# main_board.net
KiCad netlist of a schematic drawn in EAGLE
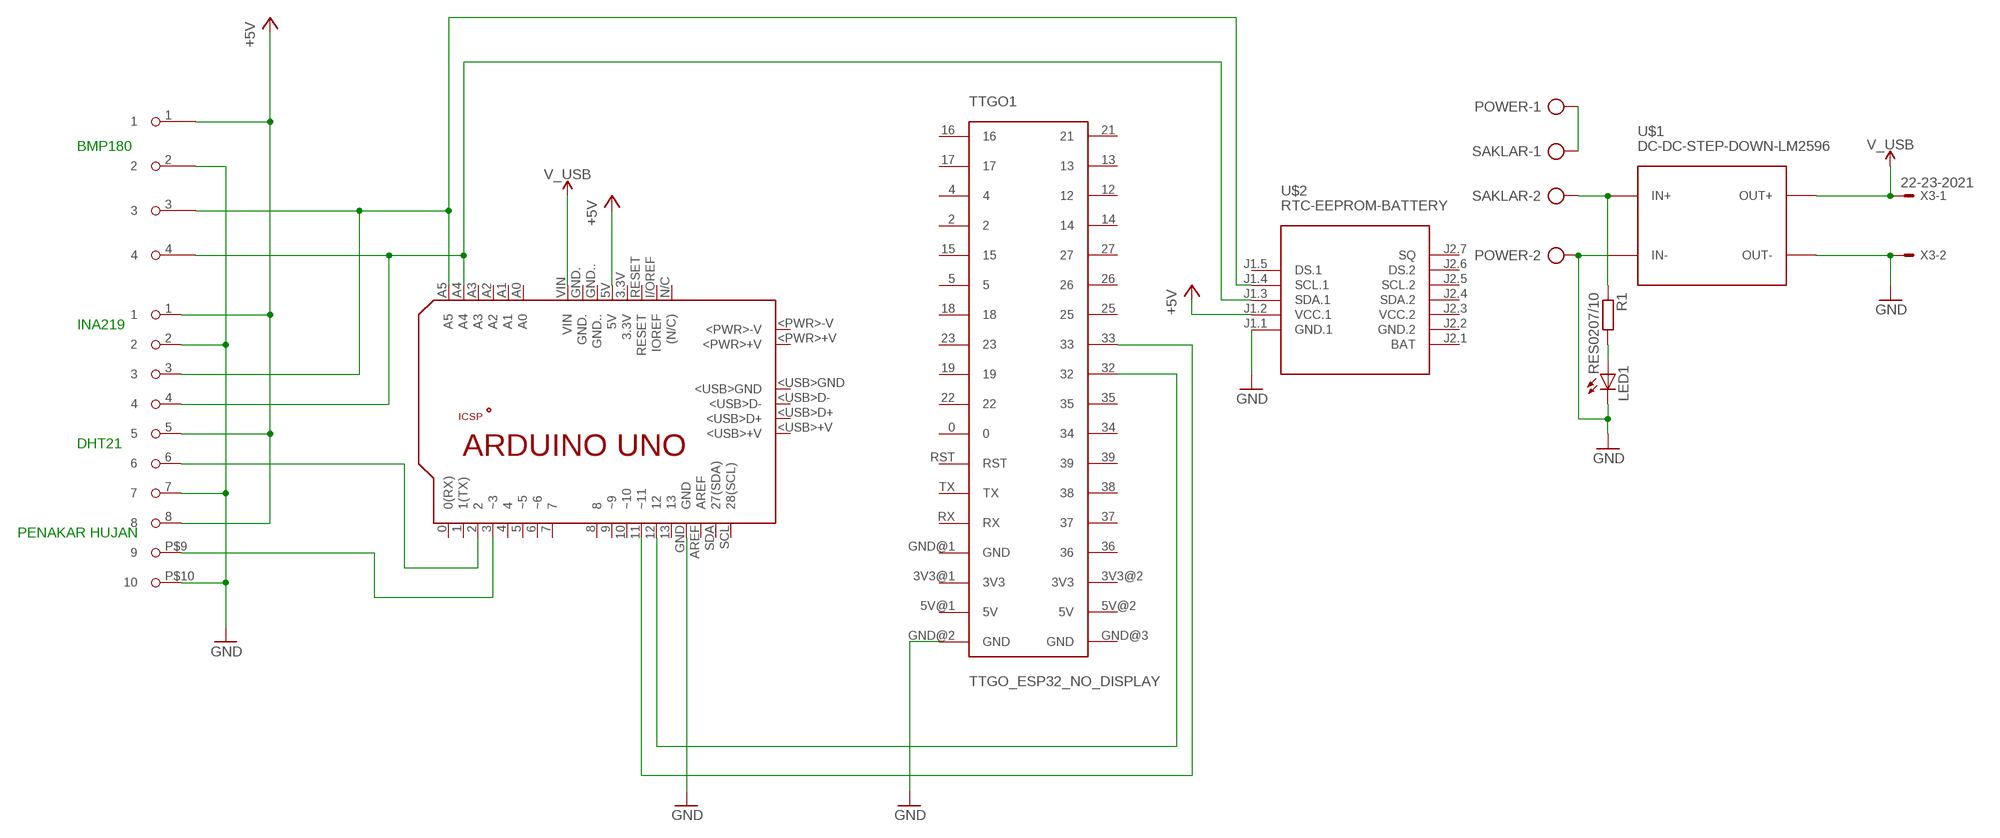
[diagram p0: schematic, sheet 1]

(export (version "E")
  (design (tool "Eeschema 10.0.6"))
  (components
    (comp (ref "LED1")
      (value "LED5MM")
      (footprint "eagle-import:LED5MM")
      (libsource (lib "eagle-import") (part "LED5MM"))
    )
    (comp (ref "PCB1")
      (value "ARDUINO_UNO")
      (footprint "eagle-import:ARDUINO_UNO")
      (libsource (lib "eagle-import") (part "ARDUINO_UNO"))
    )
    (comp (ref "POWER")
      (value "AK500/2-H")
      (footprint "eagle-import:AK500_2-H")
      (libsource (lib "eagle-import") (part "AK500/2-H"))
    )
    (comp (ref "R1")
      (value "RES0207/10")
      (footprint "eagle-import:0207_10")
      (libsource (lib "eagle-import") (part "RES0207/10"))
    )
    (comp (ref "SAKLAR")
      (value "AK500/2-H")
      (footprint "eagle-import:AK500_2-H")
      (libsource (lib "eagle-import") (part "AK500/2-H"))
    )
    (comp (ref "TTGO1")
      (value "TTGO_ESP32_NO_DISPLAY")
      (footprint "eagle-import:TTGO_ESP32_NO_DISPLAY")
      (libsource (lib "eagle-import") (part "TTGO_ESP32_NO_DISPLAY"))
    )
    (comp (ref "U$1")
      (value "DC-DC-STEP-DOWN-LM2596")
      (footprint "eagle-import:DC-DC-STEP-DOWN-LM2596")
      (libsource (lib "eagle-import") (part "DC-DC-STEP-DOWN-LM2596"))
    )
    (comp (ref "U$2")
      (value "RTC-EEPROM-BATTERY")
      (footprint "eagle-import:RTC-EEPROM-BATTERY")
      (libsource (lib "eagle-import") (part "RTC-EEPROM-BATTERY"))
    )
    (comp (ref "U$3")
      (value "CON-10TA")
      (footprint "eagle-import:CON-10TA")
      (libsource (lib "eagle-import") (part "CON-10TA"))
    )
    (comp (ref "U$4")
      (value "CON-4NEW2")
      (footprint "eagle-import:CON-4NEW")
      (libsource (lib "eagle-import") (part "CON-4NEW2"))
    )
    (comp (ref "X3")
      (value "22-23-2021")
      (footprint "eagle-import:22-23-2021")
      (fields (field (name "MF") "MOLEX"))
      (libsource (lib "eagle-import") (part "22-23-2021"))
    )
  )
  (nets
    (net (code "1") (name "+5V") (class "Default")
      (node (ref "PCB1") (pin "5V") (pinfunction "5V_5V") (pintype "bidirectional"))
      (node (ref "U$2") (pin "J1.2") (pinfunction "VCC.1_J1.2") (pintype "power_in"))
      (node (ref "U$3") (pin "1") (pinfunction "1_1") (pintype "bidirectional"))
      (node (ref "U$3") (pin "5") (pinfunction "5_5") (pintype "bidirectional"))
      (node (ref "U$3") (pin "8") (pinfunction "8_8") (pintype "bidirectional"))
      (node (ref "U$4") (pin "1") (pinfunction "1_1") (pintype "bidirectional"))
    )
    (net (code "2") (name "/GND.2") (class "Default")
      (node (ref "U$2") (pin "J2.2") (pinfunction "GND.2_J2.2") (pintype "power_in"))
    )
    (net (code "3") (name "/VCC.2") (class "Default")
      (node (ref "U$2") (pin "J2.3") (pinfunction "VCC.2_J2.3") (pintype "power_in"))
    )
    (net (code "4") (name "GND") (class "Default")
      (node (ref "LED1") (pin "K") (pinfunction "C_K") (pintype "passive"))
      (node (ref "PCB1") (pin "GND") (pinfunction "GND_GND") (pintype "bidirectional"))
      (node (ref "POWER") (pin "2") (pinfunction "KL_2") (pintype "passive"))
      (node (ref "TTGO1") (pin "GND@2") (pinfunction "GND_GND@2") (pintype "bidirectional"))
      (node (ref "U$1") (pin "IN-") (pinfunction "IN-_IN-") (pintype "bidirectional"))
      (node (ref "U$1") (pin "OUT-") (pinfunction "OUT-_OUT-") (pintype "bidirectional"))
      (node (ref "U$2") (pin "J1.1") (pinfunction "GND.1_J1.1") (pintype "power_in"))
      (node (ref "U$3") (pin "2") (pinfunction "2_2") (pintype "bidirectional"))
      (node (ref "U$3") (pin "7") (pinfunction "7_7") (pintype "bidirectional"))
      (node (ref "U$3") (pin "P$10") (pinfunction "10_P$10") (pintype "bidirectional"))
      (node (ref "U$4") (pin "2") (pinfunction "2_2") (pintype "bidirectional"))
      (node (ref "X3") (pin "2") (pinfunction "S_2") (pintype "passive"))
    )
    (net (code "5") (name "Net-(LED1-PadA)") (class "Default")
      (node (ref "LED1") (pin "A") (pinfunction "A_A") (pintype "passive"))
      (node (ref "R1") (pin "2") (pinfunction "2_2") (pintype "passive"))
    )
    (net (code "6") (name "Net-(PCB1-Pad2)") (class "Default")
      (node (ref "PCB1") (pin "2") (pinfunction "2_2") (pintype "bidirectional"))
      (node (ref "U$3") (pin "6") (pinfunction "6_6") (pintype "bidirectional"))
    )
    (net (code "7") (name "Net-(PCB1-Pad12)") (class "Default")
      (node (ref "PCB1") (pin "12") (pinfunction "12_12") (pintype "bidirectional"))
      (node (ref "TTGO1") (pin "32") (pinfunction "32_32") (pintype "bidirectional"))
    )
    (net (code "8") (name "Net-(PCB1-~{3})") (class "Default")
      (node (ref "PCB1") (pin "3") (pinfunction "~{3}_3") (pintype "bidirectional"))
      (node (ref "U$3") (pin "P$9") (pinfunction "9_P$9") (pintype "bidirectional"))
    )
    (net (code "9") (name "Net-(PCB1-~{11})") (class "Default")
      (node (ref "PCB1") (pin "11") (pinfunction "~{11}_11") (pintype "bidirectional"))
      (node (ref "TTGO1") (pin "33") (pinfunction "33_33") (pintype "bidirectional"))
    )
    (net (code "10") (name "Net-(POWERA-KL)") (class "Default")
      (node (ref "POWER") (pin "1") (pinfunction "KL_1") (pintype "passive"))
      (node (ref "SAKLAR") (pin "1") (pinfunction "KL_1") (pintype "passive"))
    )
    (net (code "11") (name "Net-(SAKLARB-KL)") (class "Default")
      (node (ref "R1") (pin "1") (pinfunction "1_1") (pintype "passive"))
      (node (ref "SAKLAR") (pin "2") (pinfunction "KL_2") (pintype "passive"))
      (node (ref "U$1") (pin "IN+") (pinfunction "IN+_IN+") (pintype "bidirectional"))
    )
    (net (code "12") (name "Net-(U$2-SCL.1)") (class "Default")
      (node (ref "PCB1") (pin "A5") (pinfunction "A5_A5") (pintype "bidirectional"))
      (node (ref "U$2") (pin "J1.4") (pinfunction "SCL.1_J1.4") (pintype "bidirectional"))
      (node (ref "U$3") (pin "3") (pinfunction "3_3") (pintype "bidirectional"))
      (node (ref "U$4") (pin "3") (pinfunction "3_3") (pintype "bidirectional"))
    )
    (net (code "13") (name "Net-(U$2-SDA.1)") (class "Default")
      (node (ref "PCB1") (pin "A4") (pinfunction "A4_A4") (pintype "bidirectional"))
      (node (ref "U$2") (pin "J1.3") (pinfunction "SDA.1_J1.3") (pintype "bidirectional"))
      (node (ref "U$3") (pin "4") (pinfunction "4_4") (pintype "bidirectional"))
      (node (ref "U$4") (pin "4") (pinfunction "4_4") (pintype "bidirectional"))
    )
    (net (code "14") (name "V_USB") (class "Default")
      (node (ref "PCB1") (pin "VIN") (pinfunction "VIN_VIN") (pintype "bidirectional"))
      (node (ref "U$1") (pin "OUT+") (pinfunction "OUT+_OUT+") (pintype "bidirectional"))
      (node (ref "X3") (pin "1") (pinfunction "S_1") (pintype "passive"))
    )
    (net (code "15") (name "unconnected-(PCB1-(N{slash}C)-PadN{slash}C)") (class "Default")
      (node (ref "PCB1") (pin "N/C") (pinfunction "(N/C)_N/C") (pintype "bidirectional"))
    )
    (net (code "16") (name "unconnected-(PCB1-0(RX)-Pad0)") (class "Default")
      (node (ref "PCB1") (pin "0") (pinfunction "0(RX)_0") (pintype "bidirectional"))
    )
    (net (code "17") (name "unconnected-(PCB1-1(TX)-Pad1)") (class "Default")
      (node (ref "PCB1") (pin "1") (pinfunction "1(TX)_1") (pintype "bidirectional"))
    )
    (net (code "18") (name "unconnected-(PCB1-27(SDA)-PadSDA)") (class "Default")
      (node (ref "PCB1") (pin "SDA") (pinfunction "27(SDA)_SDA") (pintype "bidirectional"))
    )
    (net (code "19") (name "unconnected-(PCB1-28(SCL)-PadSCL)") (class "Default")
      (node (ref "PCB1") (pin "SCL") (pinfunction "28(SCL)_SCL") (pintype "bidirectional"))
    )
    (net (code "20") (name "unconnected-(PCB1-IOREF-PadI{slash}OREF)") (class "Default")
      (node (ref "PCB1") (pin "I/OREF") (pinfunction "IOREF_I/OREF") (pintype "bidirectional"))
    )
    (net (code "21") (name "unconnected-(PCB1-Pad+5V)") (class "Default")
      (node (ref "PCB1") (pin "+5V") (pinfunction "+5V_+5V") (pintype "bidirectional"))
    )
    (net (code "22") (name "unconnected-(PCB1-Pad3.3V)") (class "Default")
      (node (ref "PCB1") (pin "3.3V") (pinfunction "3.3V_3.3V") (pintype "bidirectional"))
    )
    (net (code "23") (name "unconnected-(PCB1-Pad4)") (class "Default")
      (node (ref "PCB1") (pin "4") (pinfunction "4_4") (pintype "bidirectional"))
    )
    (net (code "24") (name "unconnected-(PCB1-Pad7)") (class "Default")
      (node (ref "PCB1") (pin "7") (pinfunction "7_7") (pintype "bidirectional"))
    )
    (net (code "25") (name "unconnected-(PCB1-Pad8)") (class "Default")
      (node (ref "PCB1") (pin "8") (pinfunction "8_8") (pintype "bidirectional"))
    )
    (net (code "26") (name "unconnected-(PCB1-Pad13)") (class "Default")
      (node (ref "PCB1") (pin "13") (pinfunction "13_13") (pintype "bidirectional"))
    )
    (net (code "27") (name "unconnected-(PCB1-Pad<PWR>+V)") (class "Default")
      (node (ref "PCB1") (pin "<PWR>+V") (pinfunction "<PWR>+V_<PWR>+V") (pintype "bidirectional"))
    )
    (net (code "28") (name "unconnected-(PCB1-Pad<PWR>-V)") (class "Default")
      (node (ref "PCB1") (pin "<PWR>-V") (pinfunction "<PWR>-V_<PWR>-V") (pintype "bidirectional"))
    )
    (net (code "29") (name "unconnected-(PCB1-Pad<USB>+V)") (class "Default")
      (node (ref "PCB1") (pin "<USB>+V") (pinfunction "<USB>+V_<USB>+V") (pintype "bidirectional"))
    )
    (net (code "30") (name "unconnected-(PCB1-Pad<USB>D+)") (class "Default")
      (node (ref "PCB1") (pin "<USB>D+") (pinfunction "<USB>D+_<USB>D+") (pintype "bidirectional"))
    )
    (net (code "31") (name "unconnected-(PCB1-Pad<USB>D-)") (class "Default")
      (node (ref "PCB1") (pin "<USB>D-") (pinfunction "<USB>D-_<USB>D-") (pintype "bidirectional"))
    )
    (net (code "32") (name "unconnected-(PCB1-Pad<USB>GND)") (class "Default")
      (node (ref "PCB1") (pin "<USB>GND") (pinfunction "<USB>GND_<USB>GND") (pintype "bidirectional"))
    )
    (net (code "33") (name "unconnected-(PCB1-PadA0)") (class "Default")
      (node (ref "PCB1") (pin "A0") (pinfunction "A0_A0") (pintype "bidirectional"))
    )
    (net (code "34") (name "unconnected-(PCB1-PadA1)") (class "Default")
      (node (ref "PCB1") (pin "A1") (pinfunction "A1_A1") (pintype "bidirectional"))
    )
    (net (code "35") (name "unconnected-(PCB1-PadA2)") (class "Default")
      (node (ref "PCB1") (pin "A2") (pinfunction "A2_A2") (pintype "bidirectional"))
    )
    (net (code "36") (name "unconnected-(PCB1-PadA3)") (class "Default")
      (node (ref "PCB1") (pin "A3") (pinfunction "A3_A3") (pintype "bidirectional"))
    )
    (net (code "37") (name "unconnected-(PCB1-PadAREF)") (class "Default")
      (node (ref "PCB1") (pin "AREF") (pinfunction "AREF_AREF") (pintype "bidirectional"))
    )
    (net (code "38") (name "unconnected-(PCB1-PadGND.)") (class "Default")
      (node (ref "PCB1") (pin "GND.") (pinfunction "GND._GND.") (pintype "bidirectional"))
    )
    (net (code "39") (name "unconnected-(PCB1-PadGND..)") (class "Default")
      (node (ref "PCB1") (pin "GND..") (pinfunction "GND.._GND..") (pintype "bidirectional"))
    )
    (net (code "40") (name "unconnected-(PCB1-PadGND_)") (class "Default")
      (node (ref "PCB1") (pin "GND_") (pinfunction "GND__GND_") (pintype "bidirectional"))
    )
    (net (code "41") (name "unconnected-(PCB1-PadMISO)") (class "Default")
      (node (ref "PCB1") (pin "MISO") (pinfunction "MISO_MISO") (pintype "bidirectional"))
    )
    (net (code "42") (name "unconnected-(PCB1-PadMOSI)") (class "Default")
      (node (ref "PCB1") (pin "MOSI") (pinfunction "MOSI_MOSI") (pintype "bidirectional"))
    )
    (net (code "43") (name "unconnected-(PCB1-PadRESET)") (class "Default")
      (node (ref "PCB1") (pin "RESET") (pinfunction "RESET_RESET") (pintype "bidirectional"))
    )
    (net (code "44") (name "unconnected-(PCB1-PadRESET.)") (class "Default")
      (node (ref "PCB1") (pin "RESET.") (pinfunction "RESET._RESET.") (pintype "bidirectional"))
    )
    (net (code "45") (name "unconnected-(PCB1-PadSCK)") (class "Default")
      (node (ref "PCB1") (pin "SCK") (pinfunction "SCK_SCK") (pintype "bidirectional"))
    )
    (net (code "46") (name "unconnected-(PCB1-~{5}-Pad5)") (class "Default")
      (node (ref "PCB1") (pin "5") (pinfunction "~{5}_5") (pintype "bidirectional"))
    )
    (net (code "47") (name "unconnected-(PCB1-~{6}-Pad6)") (class "Default")
      (node (ref "PCB1") (pin "6") (pinfunction "~{6}_6") (pintype "bidirectional"))
    )
    (net (code "48") (name "unconnected-(PCB1-~{9}-Pad9)") (class "Default")
      (node (ref "PCB1") (pin "9") (pinfunction "~{9}_9") (pintype "bidirectional"))
    )
    (net (code "49") (name "unconnected-(PCB1-~{10}-Pad10)") (class "Default")
      (node (ref "PCB1") (pin "10") (pinfunction "~{10}_10") (pintype "bidirectional"))
    )
    (net (code "50") (name "unconnected-(TTGO1-3V3-Pad3V3@1)") (class "Default")
      (node (ref "TTGO1") (pin "3V3@1") (pinfunction "3V3_3V3@1") (pintype "bidirectional"))
    )
    (net (code "51") (name "unconnected-(TTGO1-3V3-Pad3V3@2)") (class "Default")
      (node (ref "TTGO1") (pin "3V3@2") (pinfunction "3V3_3V3@2") (pintype "bidirectional"))
    )
    (net (code "52") (name "unconnected-(TTGO1-5V-Pad5V@1)") (class "Default")
      (node (ref "TTGO1") (pin "5V@1") (pinfunction "5V_5V@1") (pintype "bidirectional"))
    )
    (net (code "53") (name "unconnected-(TTGO1-5V-Pad5V@2)") (class "Default")
      (node (ref "TTGO1") (pin "5V@2") (pinfunction "5V_5V@2") (pintype "bidirectional"))
    )
    (net (code "54") (name "unconnected-(TTGO1-GND-PadGND@1)") (class "Default")
      (node (ref "TTGO1") (pin "GND@1") (pinfunction "GND_GND@1") (pintype "bidirectional"))
    )
    (net (code "55") (name "unconnected-(TTGO1-GND-PadGND@3)") (class "Default")
      (node (ref "TTGO1") (pin "GND@3") (pinfunction "GND_GND@3") (pintype "bidirectional"))
    )
    (net (code "56") (name "unconnected-(TTGO1-Pad0)") (class "Default")
      (node (ref "TTGO1") (pin "0") (pinfunction "0_0") (pintype "bidirectional"))
    )
    (net (code "57") (name "unconnected-(TTGO1-Pad2)") (class "Default")
      (node (ref "TTGO1") (pin "2") (pinfunction "2_2") (pintype "bidirectional"))
    )
    (net (code "58") (name "unconnected-(TTGO1-Pad4)") (class "Default")
      (node (ref "TTGO1") (pin "4") (pinfunction "4_4") (pintype "bidirectional"))
    )
    (net (code "59") (name "unconnected-(TTGO1-Pad5)") (class "Default")
      (node (ref "TTGO1") (pin "5") (pinfunction "5_5") (pintype "bidirectional"))
    )
    (net (code "60") (name "unconnected-(TTGO1-Pad12)") (class "Default")
      (node (ref "TTGO1") (pin "12") (pinfunction "12_12") (pintype "bidirectional"))
    )
    (net (code "61") (name "unconnected-(TTGO1-Pad13)") (class "Default")
      (node (ref "TTGO1") (pin "13") (pinfunction "13_13") (pintype "bidirectional"))
    )
    (net (code "62") (name "unconnected-(TTGO1-Pad14)") (class "Default")
      (node (ref "TTGO1") (pin "14") (pinfunction "14_14") (pintype "bidirectional"))
    )
    (net (code "63") (name "unconnected-(TTGO1-Pad15)") (class "Default")
      (node (ref "TTGO1") (pin "15") (pinfunction "15_15") (pintype "bidirectional"))
    )
    (net (code "64") (name "unconnected-(TTGO1-Pad16)") (class "Default")
      (node (ref "TTGO1") (pin "16") (pinfunction "16_16") (pintype "bidirectional"))
    )
    (net (code "65") (name "unconnected-(TTGO1-Pad17)") (class "Default")
      (node (ref "TTGO1") (pin "17") (pinfunction "17_17") (pintype "bidirectional"))
    )
    (net (code "66") (name "unconnected-(TTGO1-Pad18)") (class "Default")
      (node (ref "TTGO1") (pin "18") (pinfunction "18_18") (pintype "bidirectional"))
    )
    (net (code "67") (name "unconnected-(TTGO1-Pad19)") (class "Default")
      (node (ref "TTGO1") (pin "19") (pinfunction "19_19") (pintype "bidirectional"))
    )
    (net (code "68") (name "unconnected-(TTGO1-Pad21)") (class "Default")
      (node (ref "TTGO1") (pin "21") (pinfunction "21_21") (pintype "bidirectional"))
    )
    (net (code "69") (name "unconnected-(TTGO1-Pad22)") (class "Default")
      (node (ref "TTGO1") (pin "22") (pinfunction "22_22") (pintype "bidirectional"))
    )
    (net (code "70") (name "unconnected-(TTGO1-Pad23)") (class "Default")
      (node (ref "TTGO1") (pin "23") (pinfunction "23_23") (pintype "bidirectional"))
    )
    (net (code "71") (name "unconnected-(TTGO1-Pad25)") (class "Default")
      (node (ref "TTGO1") (pin "25") (pinfunction "25_25") (pintype "bidirectional"))
    )
    (net (code "72") (name "unconnected-(TTGO1-Pad26)") (class "Default")
      (node (ref "TTGO1") (pin "26") (pinfunction "26_26") (pintype "bidirectional"))
    )
    (net (code "73") (name "unconnected-(TTGO1-Pad27)") (class "Default")
      (node (ref "TTGO1") (pin "27") (pinfunction "27_27") (pintype "bidirectional"))
    )
    (net (code "74") (name "unconnected-(TTGO1-Pad34)") (class "Default")
      (node (ref "TTGO1") (pin "34") (pinfunction "34_34") (pintype "bidirectional"))
    )
    (net (code "75") (name "unconnected-(TTGO1-Pad35)") (class "Default")
      (node (ref "TTGO1") (pin "35") (pinfunction "35_35") (pintype "bidirectional"))
    )
    (net (code "76") (name "unconnected-(TTGO1-Pad36)") (class "Default")
      (node (ref "TTGO1") (pin "36") (pinfunction "36_36") (pintype "bidirectional"))
    )
    (net (code "77") (name "unconnected-(TTGO1-Pad37)") (class "Default")
      (node (ref "TTGO1") (pin "37") (pinfunction "37_37") (pintype "bidirectional"))
    )
    (net (code "78") (name "unconnected-(TTGO1-Pad38)") (class "Default")
      (node (ref "TTGO1") (pin "38") (pinfunction "38_38") (pintype "bidirectional"))
    )
    (net (code "79") (name "unconnected-(TTGO1-Pad39)") (class "Default")
      (node (ref "TTGO1") (pin "39") (pinfunction "39_39") (pintype "bidirectional"))
    )
    (net (code "80") (name "unconnected-(TTGO1-PadRST)") (class "Default")
      (node (ref "TTGO1") (pin "RST") (pinfunction "RST_RST") (pintype "bidirectional"))
    )
    (net (code "81") (name "unconnected-(TTGO1-PadRX)") (class "Default")
      (node (ref "TTGO1") (pin "RX") (pinfunction "RX_RX") (pintype "bidirectional"))
    )
    (net (code "82") (name "unconnected-(TTGO1-PadTX)") (class "Default")
      (node (ref "TTGO1") (pin "TX") (pinfunction "TX_TX") (pintype "bidirectional"))
    )
    (net (code "83") (name "unconnected-(U$2-BAT-PadJ2.1)") (class "Default")
      (node (ref "U$2") (pin "J2.1") (pinfunction "BAT_J2.1") (pintype "bidirectional"))
    )
    (net (code "84") (name "unconnected-(U$2-DS.1-PadJ1.5)") (class "Default")
      (node (ref "U$2") (pin "J1.5") (pinfunction "DS.1_J1.5") (pintype "bidirectional"))
    )
    (net (code "85") (name "unconnected-(U$2-DS.2-PadJ2.6)") (class "Default")
      (node (ref "U$2") (pin "J2.6") (pinfunction "DS.2_J2.6") (pintype "bidirectional"))
    )
    (net (code "86") (name "unconnected-(U$2-SCL.2-PadJ2.5)") (class "Default")
      (node (ref "U$2") (pin "J2.5") (pinfunction "SCL.2_J2.5") (pintype "bidirectional"))
    )
    (net (code "87") (name "unconnected-(U$2-SDA.2-PadJ2.4)") (class "Default")
      (node (ref "U$2") (pin "J2.4") (pinfunction "SDA.2_J2.4") (pintype "bidirectional"))
    )
    (net (code "88") (name "unconnected-(U$2-SQ-PadJ2.7)") (class "Default")
      (node (ref "U$2") (pin "J2.7") (pinfunction "SQ_J2.7") (pintype "bidirectional"))
    )
  )
)
